# motor_drivers.net
KiCad netlist of a schematic drawn in Altium Designer
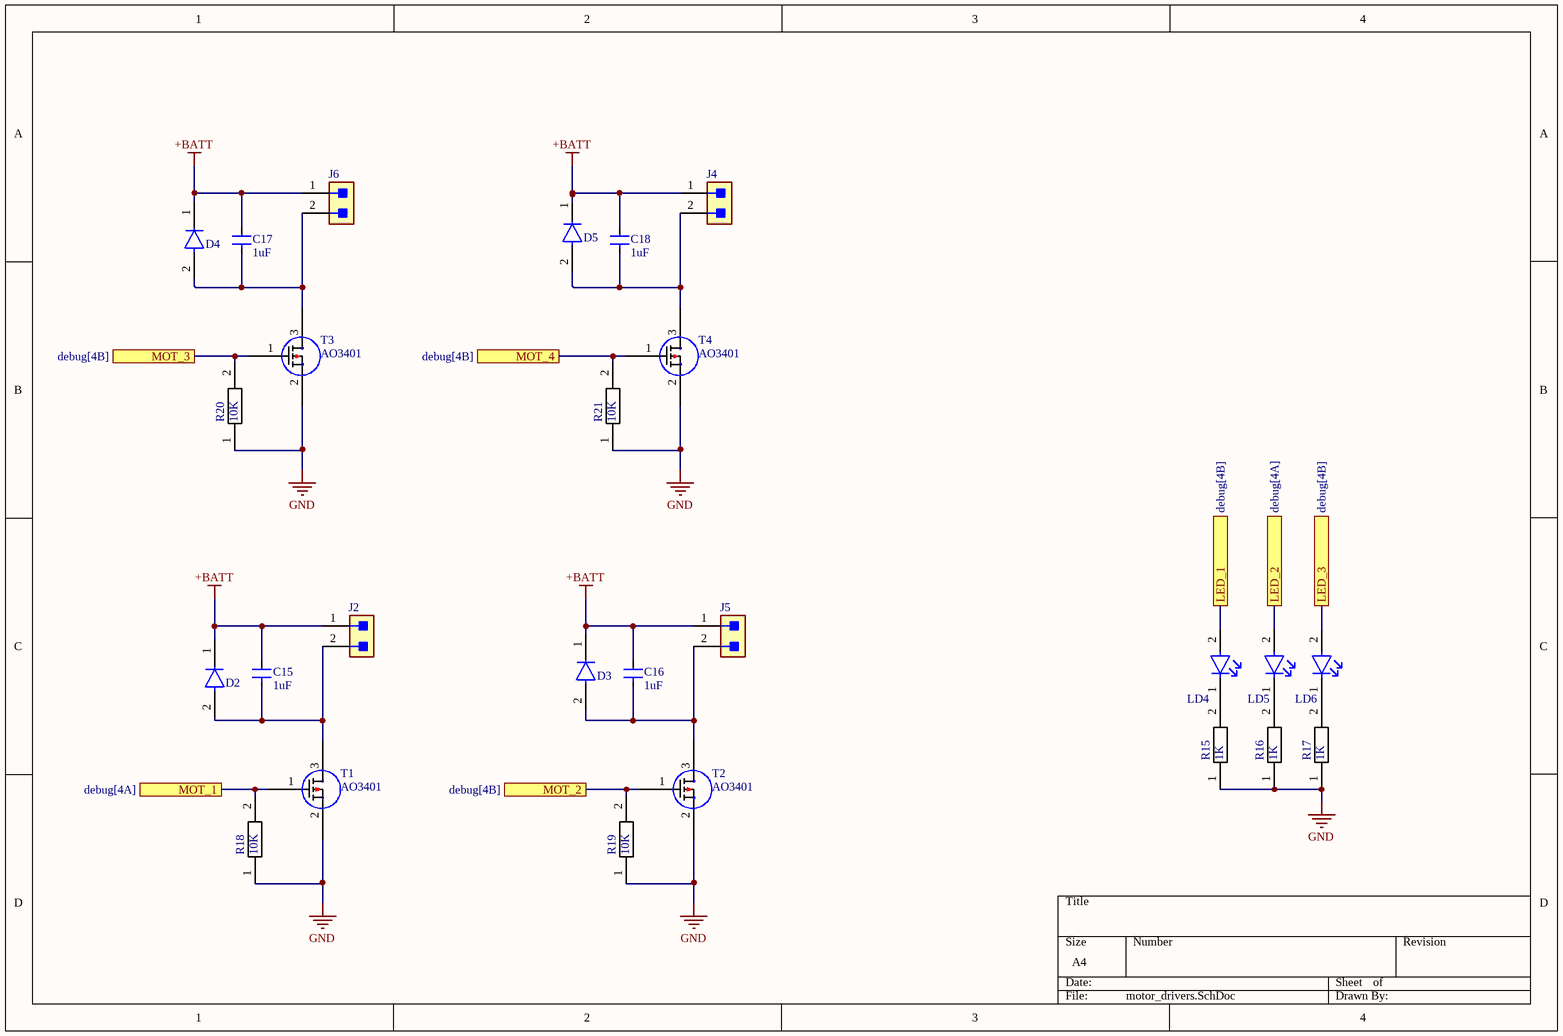
[diagram p0: motor_drivers.SchDoc]

(export (version "E")
  (design (tool "Eeschema 10.0.6"))
  (components
    (comp (ref "C15")
      (value "1uF")
      (footprint "res0805ph")
      (fields (field (name "TOLERANCE") "20%"))
      (libsource (lib "LibraryTechnologie") (part "CER Capacitor_1"))
    )
    (comp (ref "C16")
      (value "1uF")
      (footprint "res0805ph")
      (fields (field (name "TOLERANCE") "20%"))
      (libsource (lib "LibraryTechnologie") (part "CER Capacitor_1"))
    )
    (comp (ref "C17")
      (value "1uF")
      (footprint "res0805ph")
      (fields (field (name "TOLERANCE") "20%"))
      (libsource (lib "LibraryTechnologie") (part "CER Capacitor_1"))
    )
    (comp (ref "C18")
      (value "1uF")
      (footprint "res0805ph")
      (fields (field (name "TOLERANCE") "20%"))
      (libsource (lib "LibraryTechnologie") (part "CER Capacitor_1"))
    )
    (comp (ref "D2")
      (value "APT1608ZGCK")
      (footprint "SOD3715X135N")
      (description "Diode")
      (libsource (lib "Dronesch") (part "1N4148W"))
    )
    (comp (ref "D3")
      (value "APT1608ZGCK")
      (footprint "SOD3715X135N")
      (description "Diode")
      (libsource (lib "Dronesch") (part "1N4148W"))
    )
    (comp (ref "D4")
      (value "APT1608ZGCK")
      (footprint "SOD3715X135N")
      (description "Diode")
      (libsource (lib "Dronesch") (part "1N4148W"))
    )
    (comp (ref "D5")
      (value "APT1608ZGCK")
      (footprint "SOD3715X135N")
      (description "Diode")
      (libsource (lib "Dronesch") (part "1N4148W"))
    )
    (comp (ref "J2")
      (value "TMM-102-02-L-S")
      (footprint "JST_B2B-XH-A_(LF)(SN)")
      (description "CONN HEADER VERT 2POS 2MM")
      (libsource (lib "Dronesch") (part "Connector 1x2"))
    )
    (comp (ref "J4")
      (value "TMM-102-02-L-S")
      (footprint "JST_B2B-XH-A_(LF)(SN)")
      (description "CONN HEADER VERT 2POS 2MM")
      (libsource (lib "Dronesch") (part "Connector 1x2"))
    )
    (comp (ref "J5")
      (value "TMM-102-02-L-S")
      (footprint "JST_B2B-XH-A_(LF)(SN)")
      (description "CONN HEADER VERT 2POS 2MM")
      (libsource (lib "Dronesch") (part "Connector 1x2"))
    )
    (comp (ref "J6")
      (value "TMM-102-02-L-S")
      (footprint "JST_B2B-XH-A_(LF)(SN)")
      (description "CONN HEADER VERT 2POS 2MM")
      (libsource (lib "Dronesch") (part "Connector 1x2"))
    )
    (comp (ref "LD4")
      (value "APT1608ZGCK")
      (footprint "res0805ph")
      (description "LED GREEN CLEAR CHIP SMD")
      (libsource (lib "LibraryTechnologie") (part "LED"))
    )
    (comp (ref "LD5")
      (value "APT1608ZGCK")
      (footprint "res0805ph")
      (description "LED GREEN CLEAR CHIP SMD")
      (libsource (lib "LibraryTechnologie") (part "LED"))
    )
    (comp (ref "LD6")
      (value "APT1608ZGCK")
      (footprint "res0805ph")
      (description "LED GREEN CLEAR CHIP SMD")
      (libsource (lib "LibraryTechnologie") (part "LED"))
    )
    (comp (ref "R15")
      (value "1K")
      (footprint "res0805ph")
      (description "RES SMD 5.9K OHM 1% 1/4W 1206")
      (fields
        (field (name "OCTOPART") "https://octopart.com/ac1206fr-075k9l-yageo-30511161")
        (field (name "MANUFACTURER") "Yageo")
      )
      (libsource (lib "LibraryTechnologie") (part "Weerstand"))
    )
    (comp (ref "R16")
      (value "1K")
      (footprint "res0805ph")
      (description "RES SMD 5.9K OHM 1% 1/4W 1206")
      (fields
        (field (name "OCTOPART") "https://octopart.com/ac1206fr-075k9l-yageo-30511161")
        (field (name "MANUFACTURER") "Yageo")
      )
      (libsource (lib "LibraryTechnologie") (part "Weerstand"))
    )
    (comp (ref "R17")
      (value "1K")
      (footprint "res0805ph")
      (description "RES SMD 5.9K OHM 1% 1/4W 1206")
      (fields
        (field (name "OCTOPART") "https://octopart.com/ac1206fr-075k9l-yageo-30511161")
        (field (name "MANUFACTURER") "Yageo")
      )
      (libsource (lib "LibraryTechnologie") (part "Weerstand"))
    )
    (comp (ref "R18")
      (value "10K")
      (footprint "res0805ph")
      (description "RES SMD 5.9K OHM 1% 1/4W 1206")
      (fields
        (field (name "OCTOPART") "https://octopart.com/ac1206fr-075k9l-yageo-30511161")
        (field (name "MANUFACTURER") "Yageo")
      )
      (libsource (lib "LibraryTechnologie") (part "Weerstand"))
    )
    (comp (ref "R19")
      (value "10K")
      (footprint "res0805ph")
      (description "RES SMD 5.9K OHM 1% 1/4W 1206")
      (fields
        (field (name "OCTOPART") "https://octopart.com/ac1206fr-075k9l-yageo-30511161")
        (field (name "MANUFACTURER") "Yageo")
      )
      (libsource (lib "LibraryTechnologie") (part "Weerstand"))
    )
    (comp (ref "R20")
      (value "10K")
      (footprint "res0805ph")
      (description "RES SMD 5.9K OHM 1% 1/4W 1206")
      (fields
        (field (name "OCTOPART") "https://octopart.com/ac1206fr-075k9l-yageo-30511161")
        (field (name "MANUFACTURER") "Yageo")
      )
      (libsource (lib "LibraryTechnologie") (part "Weerstand"))
    )
    (comp (ref "R21")
      (value "10K")
      (footprint "res0805ph")
      (description "RES SMD 5.9K OHM 1% 1/4W 1206")
      (fields
        (field (name "OCTOPART") "https://octopart.com/ac1206fr-075k9l-yageo-30511161")
        (field (name "MANUFACTURER") "Yageo")
      )
      (libsource (lib "LibraryTechnologie") (part "Weerstand"))
    )
    (comp (ref "T1")
      (value "AO3401")
      (footprint "NXP-SOT23_N")
      (libsource (lib "Dronesch") (part "SI2302DS-T1"))
    )
    (comp (ref "T2")
      (value "AO3401")
      (footprint "NXP-SOT23_N")
      (libsource (lib "Dronesch") (part "SI2302DS-T1"))
    )
    (comp (ref "T3")
      (value "AO3401")
      (footprint "NXP-SOT23_N")
      (libsource (lib "Dronesch") (part "SI2302DS-T1"))
    )
    (comp (ref "T4")
      (value "AO3401")
      (footprint "NXP-SOT23_N")
      (libsource (lib "Dronesch") (part "SI2302DS-T1"))
    )
  )
  (nets
    (net (code "1") (name "+BATT") (class "Default")
      (node (ref "C15") (pin "2") (pinfunction "2_2") (pintype "passive"))
      (node (ref "C16") (pin "2") (pinfunction "2_2") (pintype "passive"))
      (node (ref "C17") (pin "2") (pinfunction "2_2") (pintype "passive"))
      (node (ref "C18") (pin "2") (pinfunction "2_2") (pintype "passive"))
      (node (ref "D2") (pin "1") (pinfunction "C_1") (pintype "passive"))
      (node (ref "D3") (pin "1") (pinfunction "C_1") (pintype "passive"))
      (node (ref "D4") (pin "1") (pinfunction "C_1") (pintype "passive"))
      (node (ref "D5") (pin "1") (pinfunction "C_1") (pintype "passive"))
      (node (ref "J2") (pin "1") (pinfunction "1_1") (pintype "passive"))
      (node (ref "J4") (pin "1") (pinfunction "1_1") (pintype "passive"))
      (node (ref "J5") (pin "1") (pinfunction "1_1") (pintype "passive"))
      (node (ref "J6") (pin "1") (pinfunction "1_1") (pintype "passive"))
    )
    (net (code "2") (name "/LED_1") (class "Default")
      (node (ref "LD4") (pin "2") (pinfunction "A_2") (pintype "passive"))
    )
    (net (code "3") (name "/LED_2") (class "Default")
      (node (ref "LD5") (pin "2") (pinfunction "A_2") (pintype "passive"))
    )
    (net (code "4") (name "/LED_3") (class "Default")
      (node (ref "LD6") (pin "2") (pinfunction "A_2") (pintype "passive"))
    )
    (net (code "5") (name "/MOT_1") (class "Default")
      (node (ref "R18") (pin "2") (pinfunction "2_2") (pintype "passive"))
      (node (ref "T1") (pin "1") (pinfunction "1_1") (pintype "passive"))
    )
    (net (code "6") (name "/MOT_2") (class "Default")
      (node (ref "R19") (pin "2") (pinfunction "2_2") (pintype "passive"))
      (node (ref "T2") (pin "1") (pinfunction "1_1") (pintype "passive"))
    )
    (net (code "7") (name "/MOT_3") (class "Default")
      (node (ref "R20") (pin "2") (pinfunction "2_2") (pintype "passive"))
      (node (ref "T3") (pin "1") (pinfunction "1_1") (pintype "passive"))
    )
    (net (code "8") (name "/MOT_4") (class "Default")
      (node (ref "R21") (pin "2") (pinfunction "2_2") (pintype "passive"))
      (node (ref "T4") (pin "1") (pinfunction "1_1") (pintype "passive"))
    )
    (net (code "9") (name "GND") (class "Default")
      (node (ref "R15") (pin "1") (pinfunction "1_1") (pintype "passive"))
      (node (ref "R16") (pin "1") (pinfunction "1_1") (pintype "passive"))
      (node (ref "R17") (pin "1") (pinfunction "1_1") (pintype "passive"))
      (node (ref "R18") (pin "1") (pinfunction "1_1") (pintype "passive"))
      (node (ref "R19") (pin "1") (pinfunction "1_1") (pintype "passive"))
      (node (ref "R20") (pin "1") (pinfunction "1_1") (pintype "passive"))
      (node (ref "R21") (pin "1") (pinfunction "1_1") (pintype "passive"))
      (node (ref "T1") (pin "2") (pinfunction "2_2") (pintype "passive"))
      (node (ref "T2") (pin "2") (pinfunction "2_2") (pintype "passive"))
      (node (ref "T3") (pin "2") (pinfunction "2_2") (pintype "passive"))
      (node (ref "T4") (pin "2") (pinfunction "2_2") (pintype "passive"))
    )
    (net (code "10") (name "Net-(D2-A)") (class "Default")
      (node (ref "C15") (pin "1") (pinfunction "1_1") (pintype "passive"))
      (node (ref "D2") (pin "2") (pinfunction "A_2") (pintype "passive"))
      (node (ref "J2") (pin "2") (pinfunction "2_2") (pintype "passive"))
      (node (ref "T1") (pin "3") (pinfunction "3_3") (pintype "passive"))
    )
    (net (code "11") (name "Net-(D3-A)") (class "Default")
      (node (ref "C16") (pin "1") (pinfunction "1_1") (pintype "passive"))
      (node (ref "D3") (pin "2") (pinfunction "A_2") (pintype "passive"))
      (node (ref "J5") (pin "2") (pinfunction "2_2") (pintype "passive"))
      (node (ref "T2") (pin "3") (pinfunction "3_3") (pintype "passive"))
    )
    (net (code "12") (name "Net-(D4-A)") (class "Default")
      (node (ref "C17") (pin "1") (pinfunction "1_1") (pintype "passive"))
      (node (ref "D4") (pin "2") (pinfunction "A_2") (pintype "passive"))
      (node (ref "J6") (pin "2") (pinfunction "2_2") (pintype "passive"))
      (node (ref "T3") (pin "3") (pinfunction "3_3") (pintype "passive"))
    )
    (net (code "13") (name "Net-(D5-A)") (class "Default")
      (node (ref "C18") (pin "1") (pinfunction "1_1") (pintype "passive"))
      (node (ref "D5") (pin "2") (pinfunction "A_2") (pintype "passive"))
      (node (ref "J4") (pin "2") (pinfunction "2_2") (pintype "passive"))
      (node (ref "T4") (pin "3") (pinfunction "3_3") (pintype "passive"))
    )
    (net (code "14") (name "Net-(LD4-C)") (class "Default")
      (node (ref "LD4") (pin "1") (pinfunction "C_1") (pintype "passive"))
      (node (ref "R15") (pin "2") (pinfunction "2_2") (pintype "passive"))
    )
    (net (code "15") (name "Net-(LD5-C)") (class "Default")
      (node (ref "LD5") (pin "1") (pinfunction "C_1") (pintype "passive"))
      (node (ref "R16") (pin "2") (pinfunction "2_2") (pintype "passive"))
    )
    (net (code "16") (name "Net-(LD6-C)") (class "Default")
      (node (ref "LD6") (pin "1") (pinfunction "C_1") (pintype "passive"))
      (node (ref "R17") (pin "2") (pinfunction "2_2") (pintype "passive"))
    )
  )
)
